# ProPrj_Dactyl_Manuform_-V2_1_2024-11-05.net
KiCad netlist of a schematic drawn in EasyEDA Pro
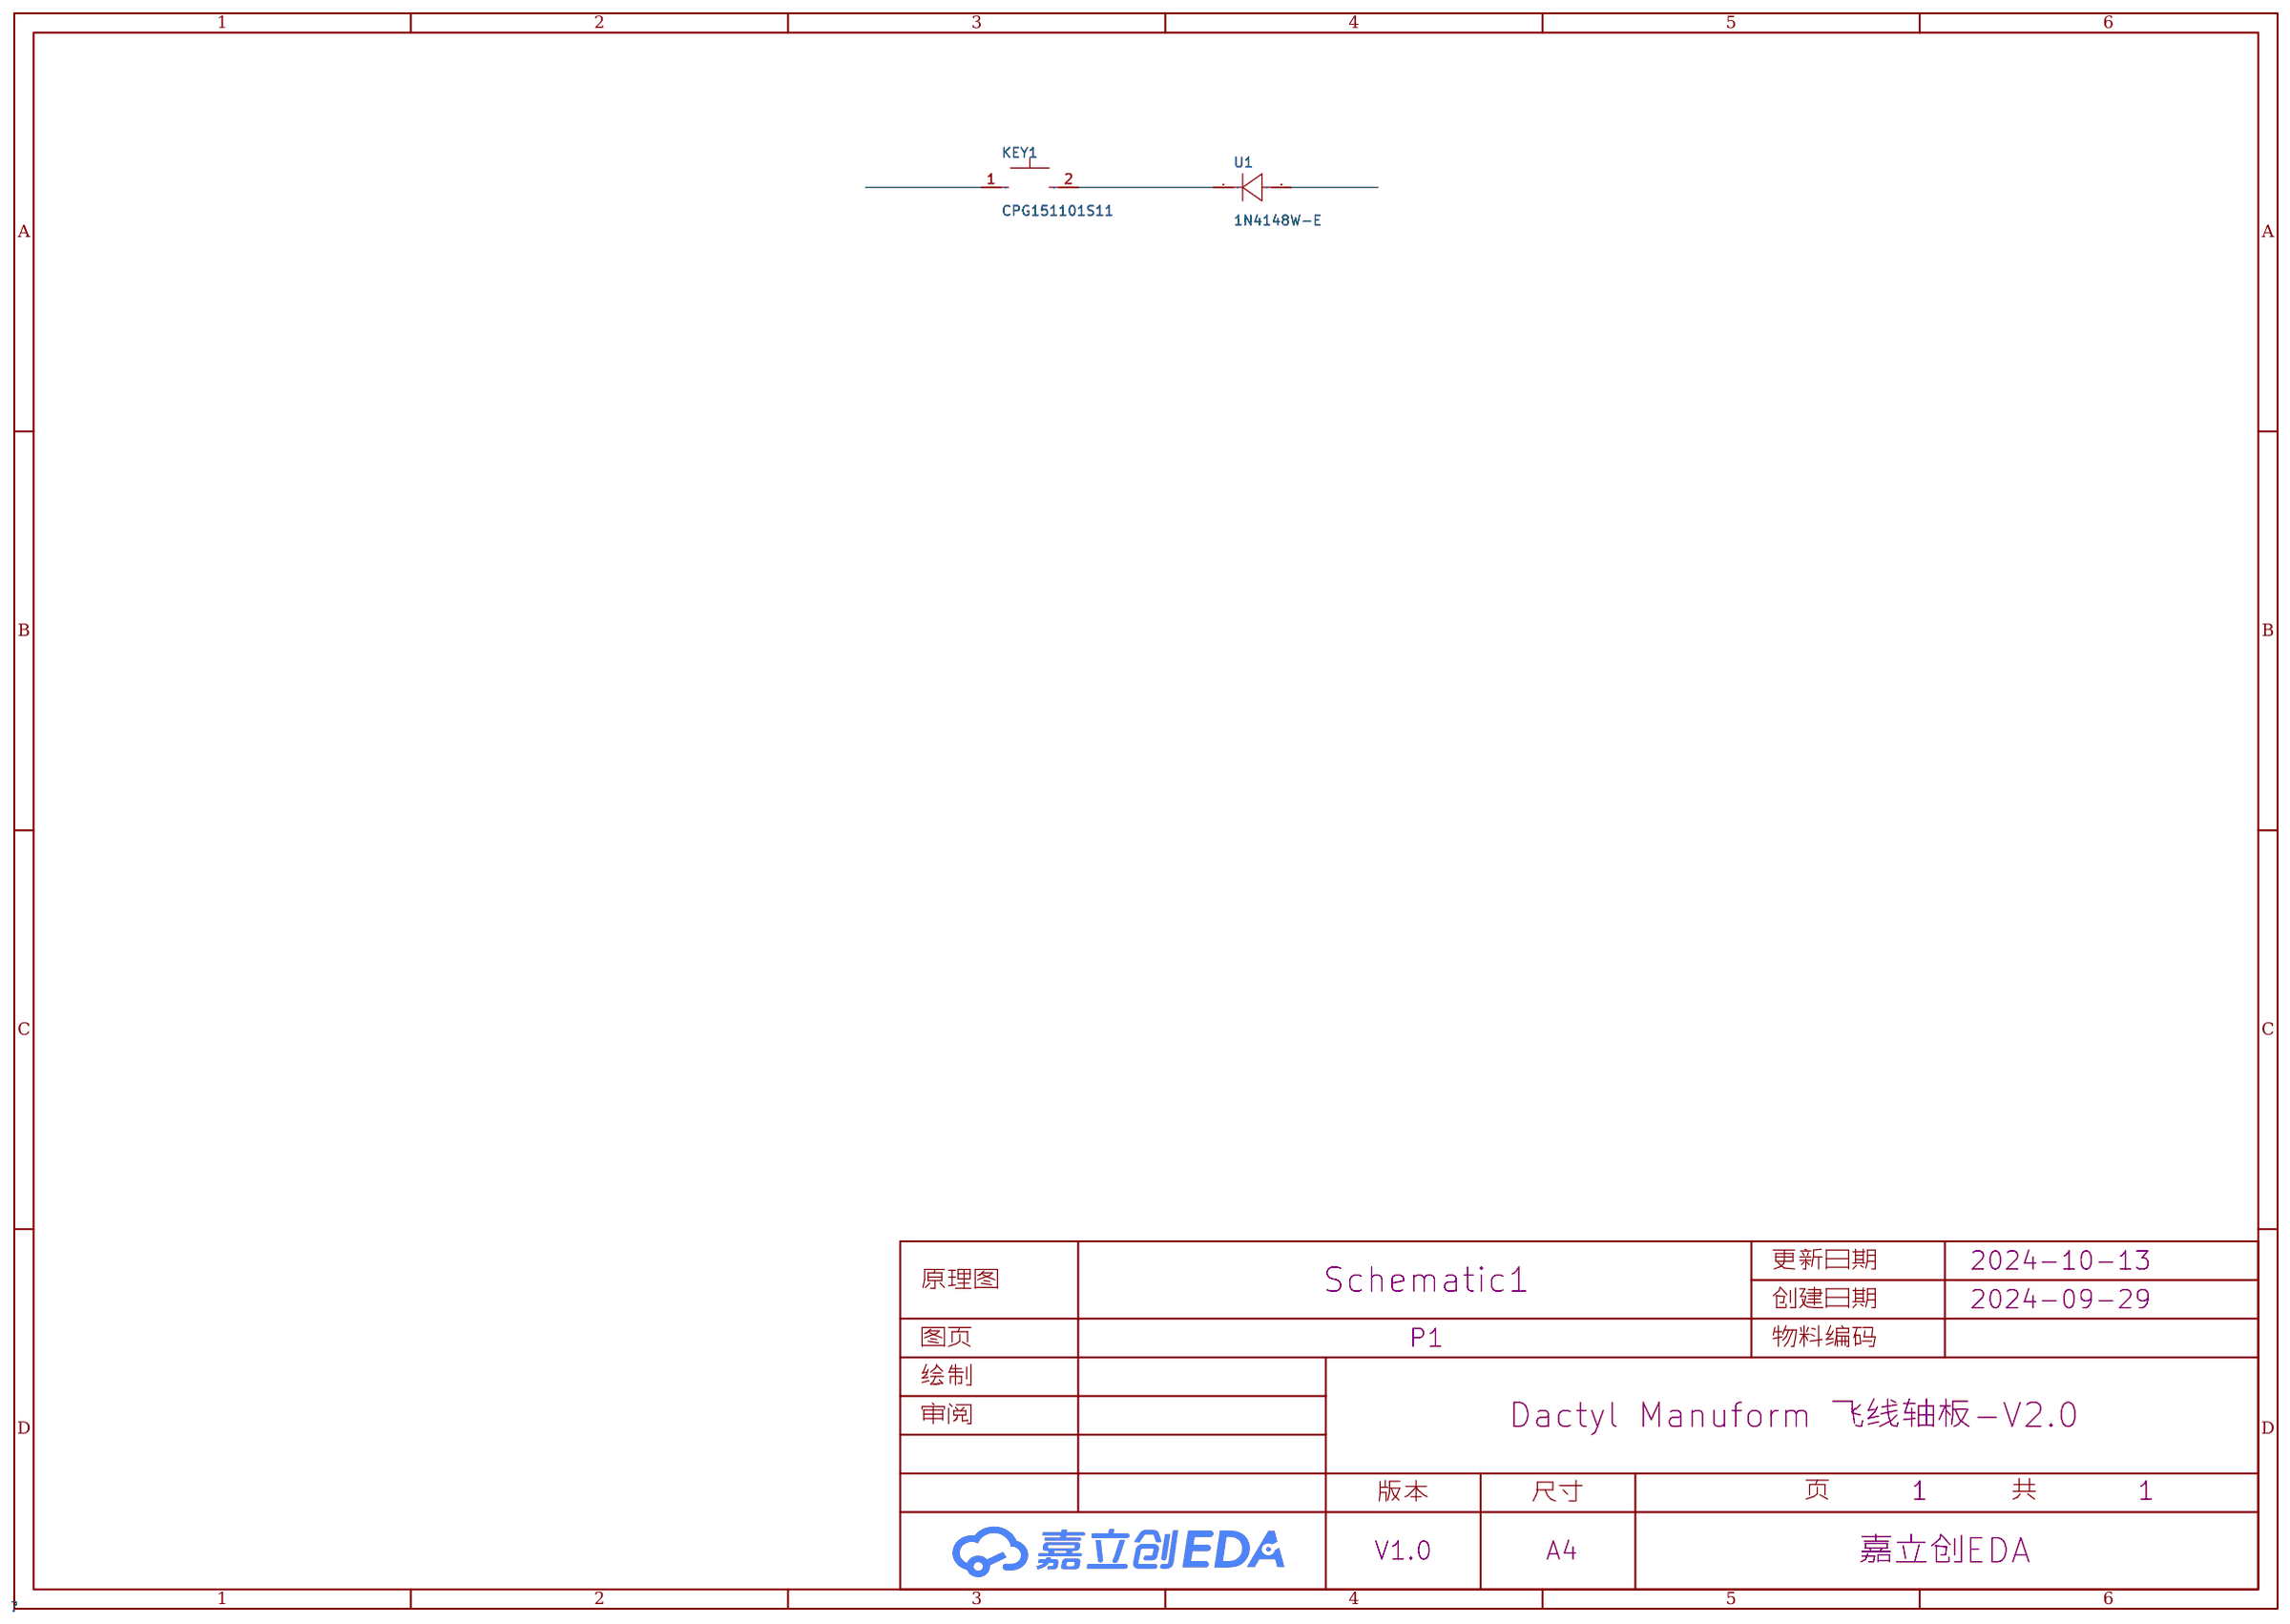
[diagram p0: schematic sheet]

(export (version "E")
  (design (tool "Eeschema 10.0.6"))
  (components
    (comp (ref "KEY1")
      (value "CPG151101S11")
      (footprint "easyedapro:TH_L10.9-W5.9-CPG151101S11")
      (description "轴类型:-;工作电压:2V~12V;针脚数:-;操作力:-;")
      (fields (field (name "Manufacturer") "Kailh(凯华)"))
      (libsource (lib "easyedapro") (part "CPG151101S11_C2803348"))
    )
    (comp (ref "U1")
      (value "1N4148W-E")
      (footprint "easyedapro:SMA_L4.3-W2.6-LS5.1-RD")
      (fields (field (name "Manufacturer") "MDD(辰达半导体)"))
      (libsource (lib "easyedapro") (part "1N4007_C9900004759"))
    )
  )
  (nets
    (net (code "1") (name "Net-(U1-K)") (class "Default")
      (node (ref "KEY1") (pin "2") (pinfunction "2_2") (pintype "input"))
      (node (ref "U1") (pin "1") (pinfunction "K_1") (pintype "unspecified"))
    )
    (net (code "2") (name "unconnected-(KEY1-Pad1)") (class "Default")
      (node (ref "KEY1") (pin "1") (pinfunction "1_1") (pintype "input"))
    )
    (net (code "3") (name "unconnected-(U1-A-Pad2)") (class "Default")
      (node (ref "U1") (pin "2") (pinfunction "A_2") (pintype "unspecified"))
    )
  )
)
